# AmbaSat-07-CCS811.net
KiCad netlist of a schematic drawn in EAGLE
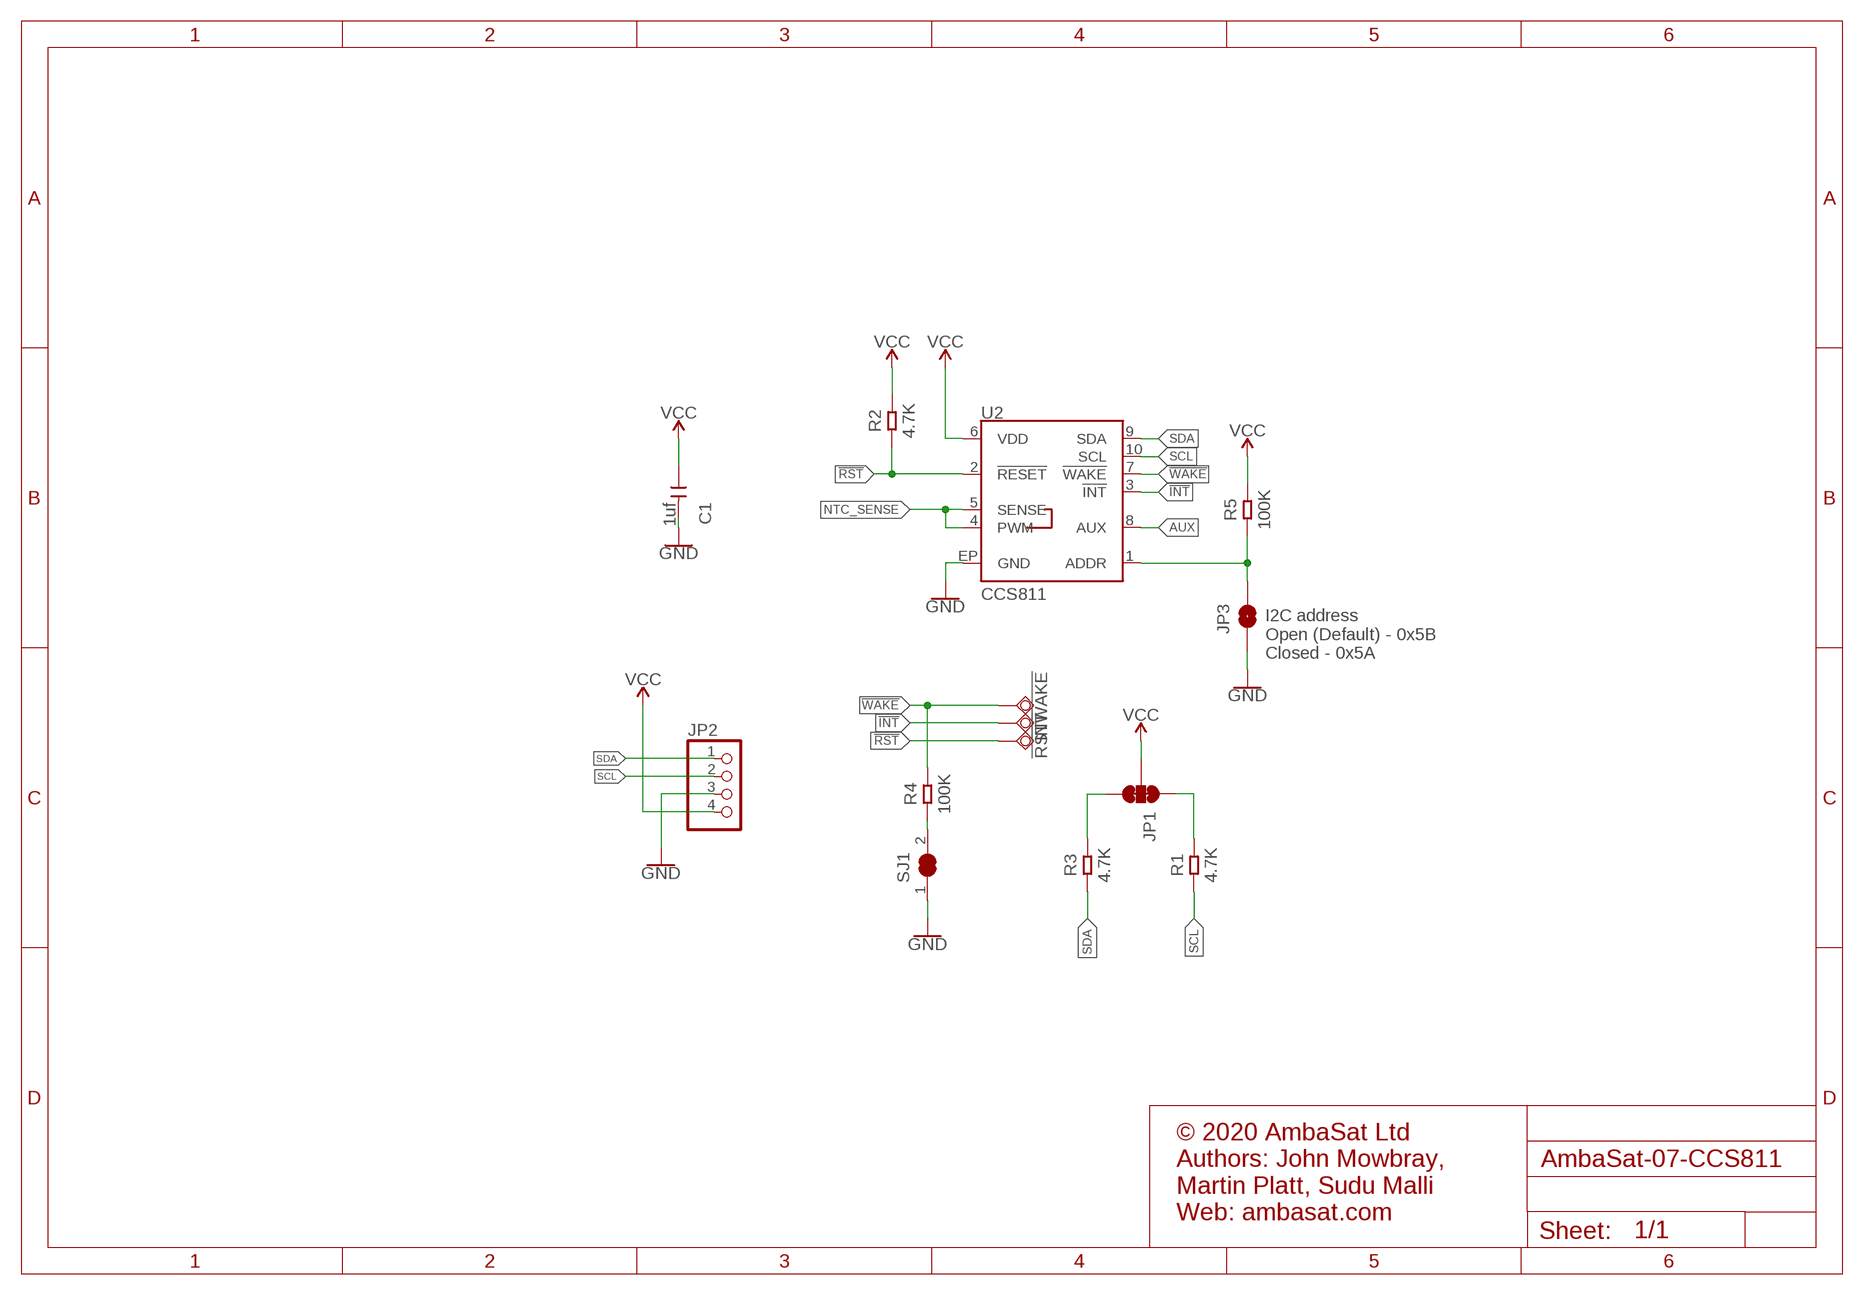
[diagram p0: schematic, sheet 1]

(export (version "E")
  (design (tool "Eeschema 10.0.6"))
  (components
    (comp (ref "!INT")
      (value "TESTPAD_TPSQTP14SQ")
      (footprint "eagle-import:TESTPAD_TP14SQ")
      (libsource (lib "eagle-import") (part "TESTPAD_TPSQTP14SQ"))
    )
    (comp (ref "!RST")
      (value "TESTPAD_TPSQTP14SQ")
      (footprint "eagle-import:TESTPAD_TP14SQ")
      (libsource (lib "eagle-import") (part "TESTPAD_TPSQTP14SQ"))
    )
    (comp (ref "!WAKE")
      (value "TESTPAD_TPSQTP14SQ")
      (footprint "eagle-import:TESTPAD_TP14SQ")
      (libsource (lib "eagle-import") (part "TESTPAD_TPSQTP14SQ"))
    )
    (comp (ref "C1")
      (value "1uf")
      (footprint "eagle-import:C0805")
      (fields (field (name "MPN") "CC0805KKX7R8BB105"))
      (libsource (lib "eagle-import") (part "CERAMIC-1UF-25V-10%-X7R(0805)"))
    )
    (comp (ref "JP1")
      (value "JUMPER-SMT_3_2-NC_TRACE_SILK")
      (footprint "eagle-import:SMT-JUMPER_3_2-NC_TRACE_SILK")
      (libsource (lib "eagle-import") (part "JUMPER-SMT_3_2-NC_TRACE_SILK"))
    )
    (comp (ref "JP2")
      (value "HEADER-1X4")
      (footprint "eagle-import:1X04_OVAL")
      (libsource (lib "eagle-import") (part "HEADER-1X4"))
    )
    (comp (ref "JP3")
      (value "JUMPER-SMT_2_NO_SILK")
      (footprint "eagle-import:SMT-JUMPER_2_NO_SILK")
      (libsource (lib "eagle-import") (part "JUMPER-SMT_2_NO_SILK"))
    )
    (comp (ref "R1")
      (value "4.7K")
      (footprint "eagle-import:R0805")
      (fields (field (name "MPN") "RC0805JR-074K7L"))
      (libsource (lib "eagle-import") (part "SMD-RES-4.7K-5%-1/8W(0805)"))
    )
    (comp (ref "R2")
      (value "4.7K")
      (footprint "eagle-import:R0805")
      (fields (field (name "MPN") "RC0805JR-074K7L"))
      (libsource (lib "eagle-import") (part "SMD-RES-4.7K-5%-1/8W(0805)"))
    )
    (comp (ref "R3")
      (value "4.7K")
      (footprint "eagle-import:R0805")
      (fields (field (name "MPN") "RC0805JR-074K7L"))
      (libsource (lib "eagle-import") (part "SMD-RES-4.7K-5%-1/8W(0805)"))
    )
    (comp (ref "R4")
      (value "100K")
      (footprint "eagle-import:R0805")
      (fields (field (name "MPN") "RC0805FR-0710KL"))
      (libsource (lib "eagle-import") (part "SMD-RES-10K-1%-1/8W(0805)"))
    )
    (comp (ref "R5")
      (value "100K")
      (footprint "eagle-import:R0805")
      (fields (field (name "MPN") "RC0805FR-0710KL"))
      (libsource (lib "eagle-import") (part "SMD-RES-10K-1%-1/8W(0805)"))
    )
    (comp (ref "SJ1")
      (value "SOLDERJUMPER_CLOSED")
      (footprint "eagle-import:SOLDERJUMPER_CLOSEDWIRE")
      (libsource (lib "eagle-import") (part "SOLDERJUMPER_CLOSED"))
    )
    (comp (ref "U2")
      (value "CCS811")
      (footprint "eagle-import:LGA10")
      (libsource (lib "eagle-import") (part "CCS811"))
    )
  )
  (nets
    (net (code "1") (name "/~{INT}") (class "Default")
      (node (ref "!INT") (pin "TP") (pinfunction "TP_TP") (pintype "input"))
      (node (ref "U2") (pin "3") (pinfunction "~{INT}_3") (pintype "bidirectional"))
    )
    (net (code "2") (name "/~{RST}") (class "Default")
      (node (ref "!RST") (pin "TP") (pinfunction "TP_TP") (pintype "input"))
      (node (ref "R2") (pin "1") (pinfunction "1_1") (pintype "passive"))
      (node (ref "U2") (pin "2") (pinfunction "~{RESET}_2") (pintype "bidirectional"))
    )
    (net (code "3") (name "/~{WAKE}") (class "Default")
      (node (ref "!WAKE") (pin "TP") (pinfunction "TP_TP") (pintype "input"))
      (node (ref "R4") (pin "2") (pinfunction "2_2") (pintype "passive"))
      (node (ref "U2") (pin "7") (pinfunction "~{WAKE}_7") (pintype "bidirectional"))
    )
    (net (code "4") (name "AUX") (class "Default")
      (node (ref "U2") (pin "8") (pinfunction "AUX_8") (pintype "bidirectional"))
    )
    (net (code "5") (name "GND") (class "Default")
      (node (ref "C1") (pin "2") (pinfunction "2_2") (pintype "passive"))
      (node (ref "JP2") (pin "3") (pinfunction "3_3") (pintype "passive"))
      (node (ref "JP3") (pin "1") (pinfunction "1_1") (pintype "passive"))
      (node (ref "SJ1") (pin "1") (pinfunction "1_1") (pintype "passive"))
      (node (ref "U2") (pin "EP") (pinfunction "GND_EP") (pintype "bidirectional"))
    )
    (net (code "6") (name "NTC_SENSE") (class "Default")
      (node (ref "U2") (pin "4") (pinfunction "PWM_4") (pintype "bidirectional"))
      (node (ref "U2") (pin "5") (pinfunction "SENSE_5") (pintype "bidirectional"))
    )
    (net (code "7") (name "Net-(JP1-Pad1)") (class "Default")
      (node (ref "JP1") (pin "1") (pinfunction "1_1") (pintype "passive"))
      (node (ref "R1") (pin "2") (pinfunction "2_2") (pintype "passive"))
    )
    (net (code "8") (name "Net-(JP1-Pad3)") (class "Default")
      (node (ref "JP1") (pin "3") (pinfunction "3_3") (pintype "passive"))
      (node (ref "R3") (pin "2") (pinfunction "2_2") (pintype "passive"))
    )
    (net (code "9") (name "Net-(R4-Pad1)") (class "Default")
      (node (ref "R4") (pin "1") (pinfunction "1_1") (pintype "passive"))
      (node (ref "SJ1") (pin "2") (pinfunction "2_2") (pintype "passive"))
    )
    (net (code "10") (name "Net-(U2-ADDR)") (class "Default")
      (node (ref "JP3") (pin "2") (pinfunction "2_2") (pintype "passive"))
      (node (ref "R5") (pin "1") (pinfunction "1_1") (pintype "passive"))
      (node (ref "U2") (pin "1") (pinfunction "ADDR_1") (pintype "bidirectional"))
    )
    (net (code "11") (name "SCL") (class "Default")
      (node (ref "JP2") (pin "2") (pinfunction "2_2") (pintype "passive"))
      (node (ref "R1") (pin "1") (pinfunction "1_1") (pintype "passive"))
      (node (ref "U2") (pin "10") (pinfunction "SCL_10") (pintype "bidirectional"))
    )
    (net (code "12") (name "SDA") (class "Default")
      (node (ref "JP2") (pin "1") (pinfunction "1_1") (pintype "passive"))
      (node (ref "R3") (pin "1") (pinfunction "1_1") (pintype "passive"))
      (node (ref "U2") (pin "9") (pinfunction "SDA_9") (pintype "bidirectional"))
    )
    (net (code "13") (name "VCC") (class "Default")
      (node (ref "C1") (pin "1") (pinfunction "1_1") (pintype "passive"))
      (node (ref "JP1") (pin "2") (pinfunction "2_2") (pintype "passive"))
      (node (ref "JP2") (pin "4") (pinfunction "4_4") (pintype "passive"))
      (node (ref "R2") (pin "2") (pinfunction "2_2") (pintype "passive"))
      (node (ref "R5") (pin "2") (pinfunction "2_2") (pintype "passive"))
      (node (ref "U2") (pin "6") (pinfunction "VDD_6") (pintype "bidirectional"))
    )
  )
)
